# wssf_arduino_nano_server.net
KiCad netlist of a schematic drawn in EAGLE
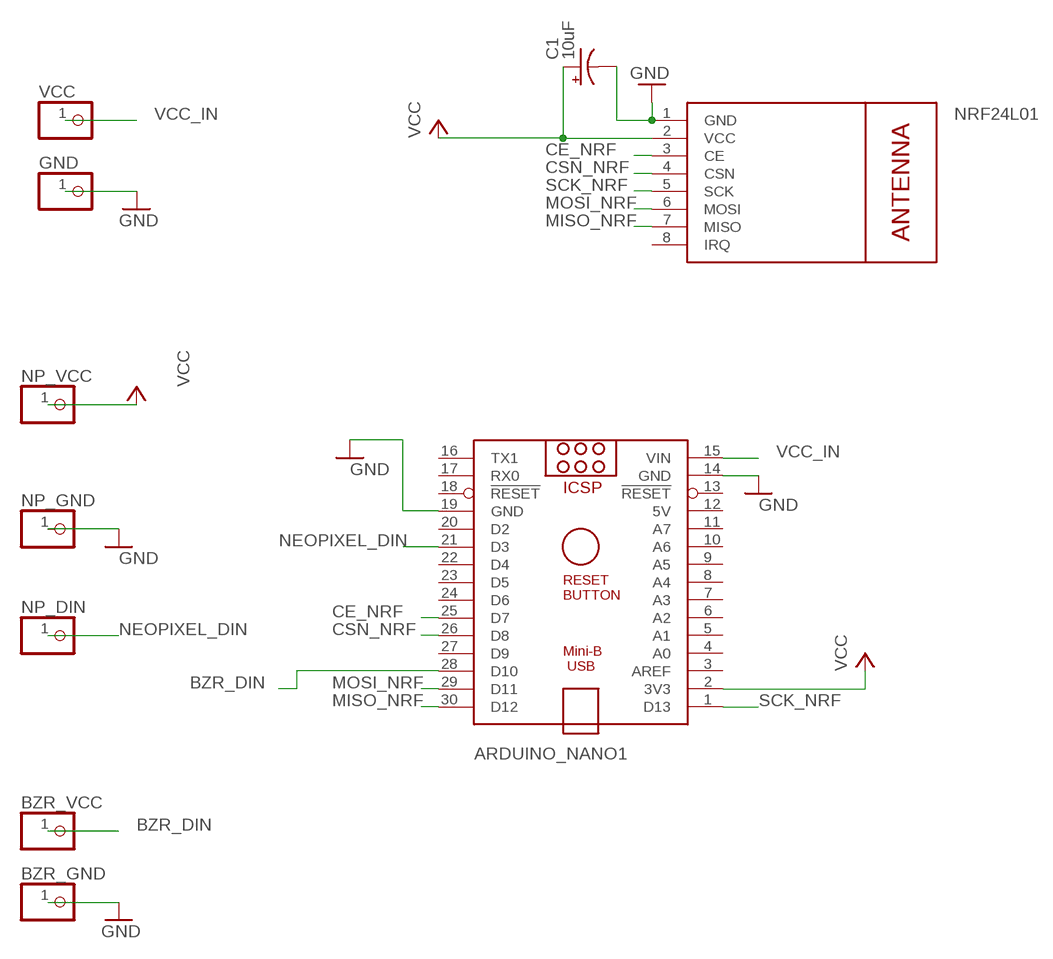
[diagram p0: schematic, sheet 1]

(export (version "E")
  (design (tool "Eeschema 10.0.6"))
  (components
    (comp (ref "ARDUINO_NANO1")
      (value "ARDUINO_NANO")
      (footprint "eagle-import:ARDUINO_NANO")
      (libsource (lib "eagle-import") (part "ARDUINO_NANO"))
    )
    (comp (ref "BZR_GND")
      (value "PINHD-1X1")
      (footprint "eagle-import:1X01")
      (libsource (lib "eagle-import") (part "PINHD-1X1"))
    )
    (comp (ref "BZR_VCC")
      (value "PINHD-1X1")
      (footprint "eagle-import:1X01")
      (libsource (lib "eagle-import") (part "PINHD-1X1"))
    )
    (comp (ref "C1")
      (value "10uF")
      (footprint "eagle-import:E2-5")
      (libsource (lib "eagle-import") (part "CPOL-USE2-5"))
    )
    (comp (ref "GND")
      (value "PINHD-1X1")
      (footprint "eagle-import:1X01")
      (libsource (lib "eagle-import") (part "PINHD-1X1"))
    )
    (comp (ref "NP_DIN")
      (value "PINHD-1X1")
      (footprint "eagle-import:1X01")
      (libsource (lib "eagle-import") (part "PINHD-1X1"))
    )
    (comp (ref "NP_GND")
      (value "PINHD-1X1")
      (footprint "eagle-import:1X01")
      (libsource (lib "eagle-import") (part "PINHD-1X1"))
    )
    (comp (ref "NP_VCC")
      (value "PINHD-1X1")
      (footprint "eagle-import:1X01")
      (libsource (lib "eagle-import") (part "PINHD-1X1"))
    )
    (comp (ref "NRF24L01")
      (value "WIRELESS-NRF24L01")
      (footprint "eagle-import:WIRELESS-NRF24L01")
      (libsource (lib "eagle-import") (part "WIRELESS-NRF24L01"))
    )
    (comp (ref "VCC")
      (value "PINHD-1X1")
      (footprint "eagle-import:1X01")
      (libsource (lib "eagle-import") (part "PINHD-1X1"))
    )
  )
  (nets
    (net (code "1") (name "/5V") (class "Default")
      (node (ref "ARDUINO_NANO1") (pin "12") (pinfunction "5V_12") (pintype "power_in"))
    )
    (net (code "2") (name "/BZR_DIN") (class "Default")
      (node (ref "ARDUINO_NANO1") (pin "28") (pinfunction "D10_28") (pintype "bidirectional"))
      (node (ref "BZR_VCC") (pin "1") (pinfunction "1_1") (pintype "passive"))
    )
    (net (code "3") (name "/CE_NRF") (class "Default")
      (node (ref "ARDUINO_NANO1") (pin "25") (pinfunction "D7_25") (pintype "bidirectional"))
      (node (ref "NRF24L01") (pin "3") (pinfunction "CE_3") (pintype "bidirectional"))
    )
    (net (code "4") (name "/CSN_NRF") (class "Default")
      (node (ref "ARDUINO_NANO1") (pin "26") (pinfunction "D8_26") (pintype "bidirectional"))
      (node (ref "NRF24L01") (pin "4") (pinfunction "CSN_4") (pintype "bidirectional"))
    )
    (net (code "5") (name "/MISO_NRF") (class "Default")
      (node (ref "ARDUINO_NANO1") (pin "30") (pinfunction "D12_30") (pintype "bidirectional"))
      (node (ref "NRF24L01") (pin "7") (pinfunction "MISO_7") (pintype "bidirectional"))
    )
    (net (code "6") (name "/MOSI_NRF") (class "Default")
      (node (ref "ARDUINO_NANO1") (pin "29") (pinfunction "D11_29") (pintype "bidirectional"))
      (node (ref "NRF24L01") (pin "6") (pinfunction "MOSI_6") (pintype "bidirectional"))
    )
    (net (code "7") (name "/NEOPIXEL_DIN") (class "Default")
      (node (ref "ARDUINO_NANO1") (pin "21") (pinfunction "D3_21") (pintype "bidirectional"))
      (node (ref "NP_DIN") (pin "1") (pinfunction "1_1") (pintype "passive"))
    )
    (net (code "8") (name "/SCK_NRF") (class "Default")
      (node (ref "ARDUINO_NANO1") (pin "1") (pinfunction "D13_1") (pintype "bidirectional"))
      (node (ref "NRF24L01") (pin "5") (pinfunction "SCK_5") (pintype "bidirectional"))
    )
    (net (code "9") (name "/VCC_IN") (class "Default")
      (node (ref "ARDUINO_NANO1") (pin "15") (pinfunction "VIN_15") (pintype "power_in"))
      (node (ref "VCC") (pin "1") (pinfunction "1_1") (pintype "passive"))
    )
    (net (code "10") (name "GND") (class "Default")
      (node (ref "ARDUINO_NANO1") (pin "14") (pinfunction "GND_14") (pintype "power_in"))
      (node (ref "ARDUINO_NANO1") (pin "19") (pinfunction "GND_19") (pintype "power_in"))
      (node (ref "BZR_GND") (pin "1") (pinfunction "1_1") (pintype "passive"))
      (node (ref "C1") (pin "-") (pinfunction "-_-") (pintype "passive"))
      (node (ref "GND") (pin "1") (pinfunction "1_1") (pintype "passive"))
      (node (ref "NP_GND") (pin "1") (pinfunction "1_1") (pintype "passive"))
      (node (ref "NRF24L01") (pin "1") (pinfunction "GND_1") (pintype "power_in"))
    )
    (net (code "11") (name "VCC") (class "Default")
      (node (ref "ARDUINO_NANO1") (pin "2") (pinfunction "3V3_2") (pintype "output"))
      (node (ref "C1") (pin "+") (pinfunction "+_+") (pintype "passive"))
      (node (ref "NP_VCC") (pin "1") (pinfunction "1_1") (pintype "passive"))
      (node (ref "NRF24L01") (pin "2") (pinfunction "VCC_2") (pintype "power_in"))
    )
    (net (code "12") (name "unconnected-(ARDUINO_NANO1-A0-Pad4)") (class "Default")
      (node (ref "ARDUINO_NANO1") (pin "4") (pinfunction "A0_4") (pintype "bidirectional"))
    )
    (net (code "13") (name "unconnected-(ARDUINO_NANO1-A1-Pad5)") (class "Default")
      (node (ref "ARDUINO_NANO1") (pin "5") (pinfunction "A1_5") (pintype "bidirectional"))
    )
    (net (code "14") (name "unconnected-(ARDUINO_NANO1-A2-Pad6)") (class "Default")
      (node (ref "ARDUINO_NANO1") (pin "6") (pinfunction "A2_6") (pintype "bidirectional"))
    )
    (net (code "15") (name "unconnected-(ARDUINO_NANO1-A3-Pad7)") (class "Default")
      (node (ref "ARDUINO_NANO1") (pin "7") (pinfunction "A3_7") (pintype "bidirectional"))
    )
    (net (code "16") (name "unconnected-(ARDUINO_NANO1-A4-Pad8)") (class "Default")
      (node (ref "ARDUINO_NANO1") (pin "8") (pinfunction "A4_8") (pintype "bidirectional"))
    )
    (net (code "17") (name "unconnected-(ARDUINO_NANO1-A5-Pad9)") (class "Default")
      (node (ref "ARDUINO_NANO1") (pin "9") (pinfunction "A5_9") (pintype "bidirectional"))
    )
    (net (code "18") (name "unconnected-(ARDUINO_NANO1-A6-Pad10)") (class "Default")
      (node (ref "ARDUINO_NANO1") (pin "10") (pinfunction "A6_10") (pintype "bidirectional"))
    )
    (net (code "19") (name "unconnected-(ARDUINO_NANO1-A7-Pad11)") (class "Default")
      (node (ref "ARDUINO_NANO1") (pin "11") (pinfunction "A7_11") (pintype "bidirectional"))
    )
    (net (code "20") (name "unconnected-(ARDUINO_NANO1-AREF-Pad3)") (class "Default")
      (node (ref "ARDUINO_NANO1") (pin "3") (pinfunction "AREF_3") (pintype "input"))
    )
    (net (code "21") (name "unconnected-(ARDUINO_NANO1-D2-Pad20)") (class "Default")
      (node (ref "ARDUINO_NANO1") (pin "20") (pinfunction "D2_20") (pintype "bidirectional"))
    )
    (net (code "22") (name "unconnected-(ARDUINO_NANO1-D4-Pad22)") (class "Default")
      (node (ref "ARDUINO_NANO1") (pin "22") (pinfunction "D4_22") (pintype "bidirectional"))
    )
    (net (code "23") (name "unconnected-(ARDUINO_NANO1-D5-Pad23)") (class "Default")
      (node (ref "ARDUINO_NANO1") (pin "23") (pinfunction "D5_23") (pintype "bidirectional"))
    )
    (net (code "24") (name "unconnected-(ARDUINO_NANO1-D6-Pad24)") (class "Default")
      (node (ref "ARDUINO_NANO1") (pin "24") (pinfunction "D6_24") (pintype "bidirectional"))
    )
    (net (code "25") (name "unconnected-(ARDUINO_NANO1-D9-Pad27)") (class "Default")
      (node (ref "ARDUINO_NANO1") (pin "27") (pinfunction "D9_27") (pintype "bidirectional"))
    )
    (net (code "26") (name "unconnected-(ARDUINO_NANO1-RX0-Pad17)") (class "Default")
      (node (ref "ARDUINO_NANO1") (pin "17") (pinfunction "RX0_17") (pintype "bidirectional"))
    )
    (net (code "27") (name "unconnected-(ARDUINO_NANO1-TX1-Pad16)") (class "Default")
      (node (ref "ARDUINO_NANO1") (pin "16") (pinfunction "TX1_16") (pintype "bidirectional"))
    )
    (net (code "28") (name "unconnected-(ARDUINO_NANO1-~{RESET}-Pad13)") (class "Default")
      (node (ref "ARDUINO_NANO1") (pin "13") (pinfunction "~{RESET}_13") (pintype "input"))
    )
    (net (code "29") (name "unconnected-(ARDUINO_NANO1-~{RESET}-Pad18)") (class "Default")
      (node (ref "ARDUINO_NANO1") (pin "18") (pinfunction "~{RESET}_18") (pintype "input"))
    )
    (net (code "30") (name "unconnected-(NRF24L01-IRQ-Pad8)") (class "Default")
      (node (ref "NRF24L01") (pin "8") (pinfunction "IRQ_8") (pintype "bidirectional"))
    )
  )
)
